# IC555timer.net
KiCad netlist of a schematic drawn in EasyEDA Pro
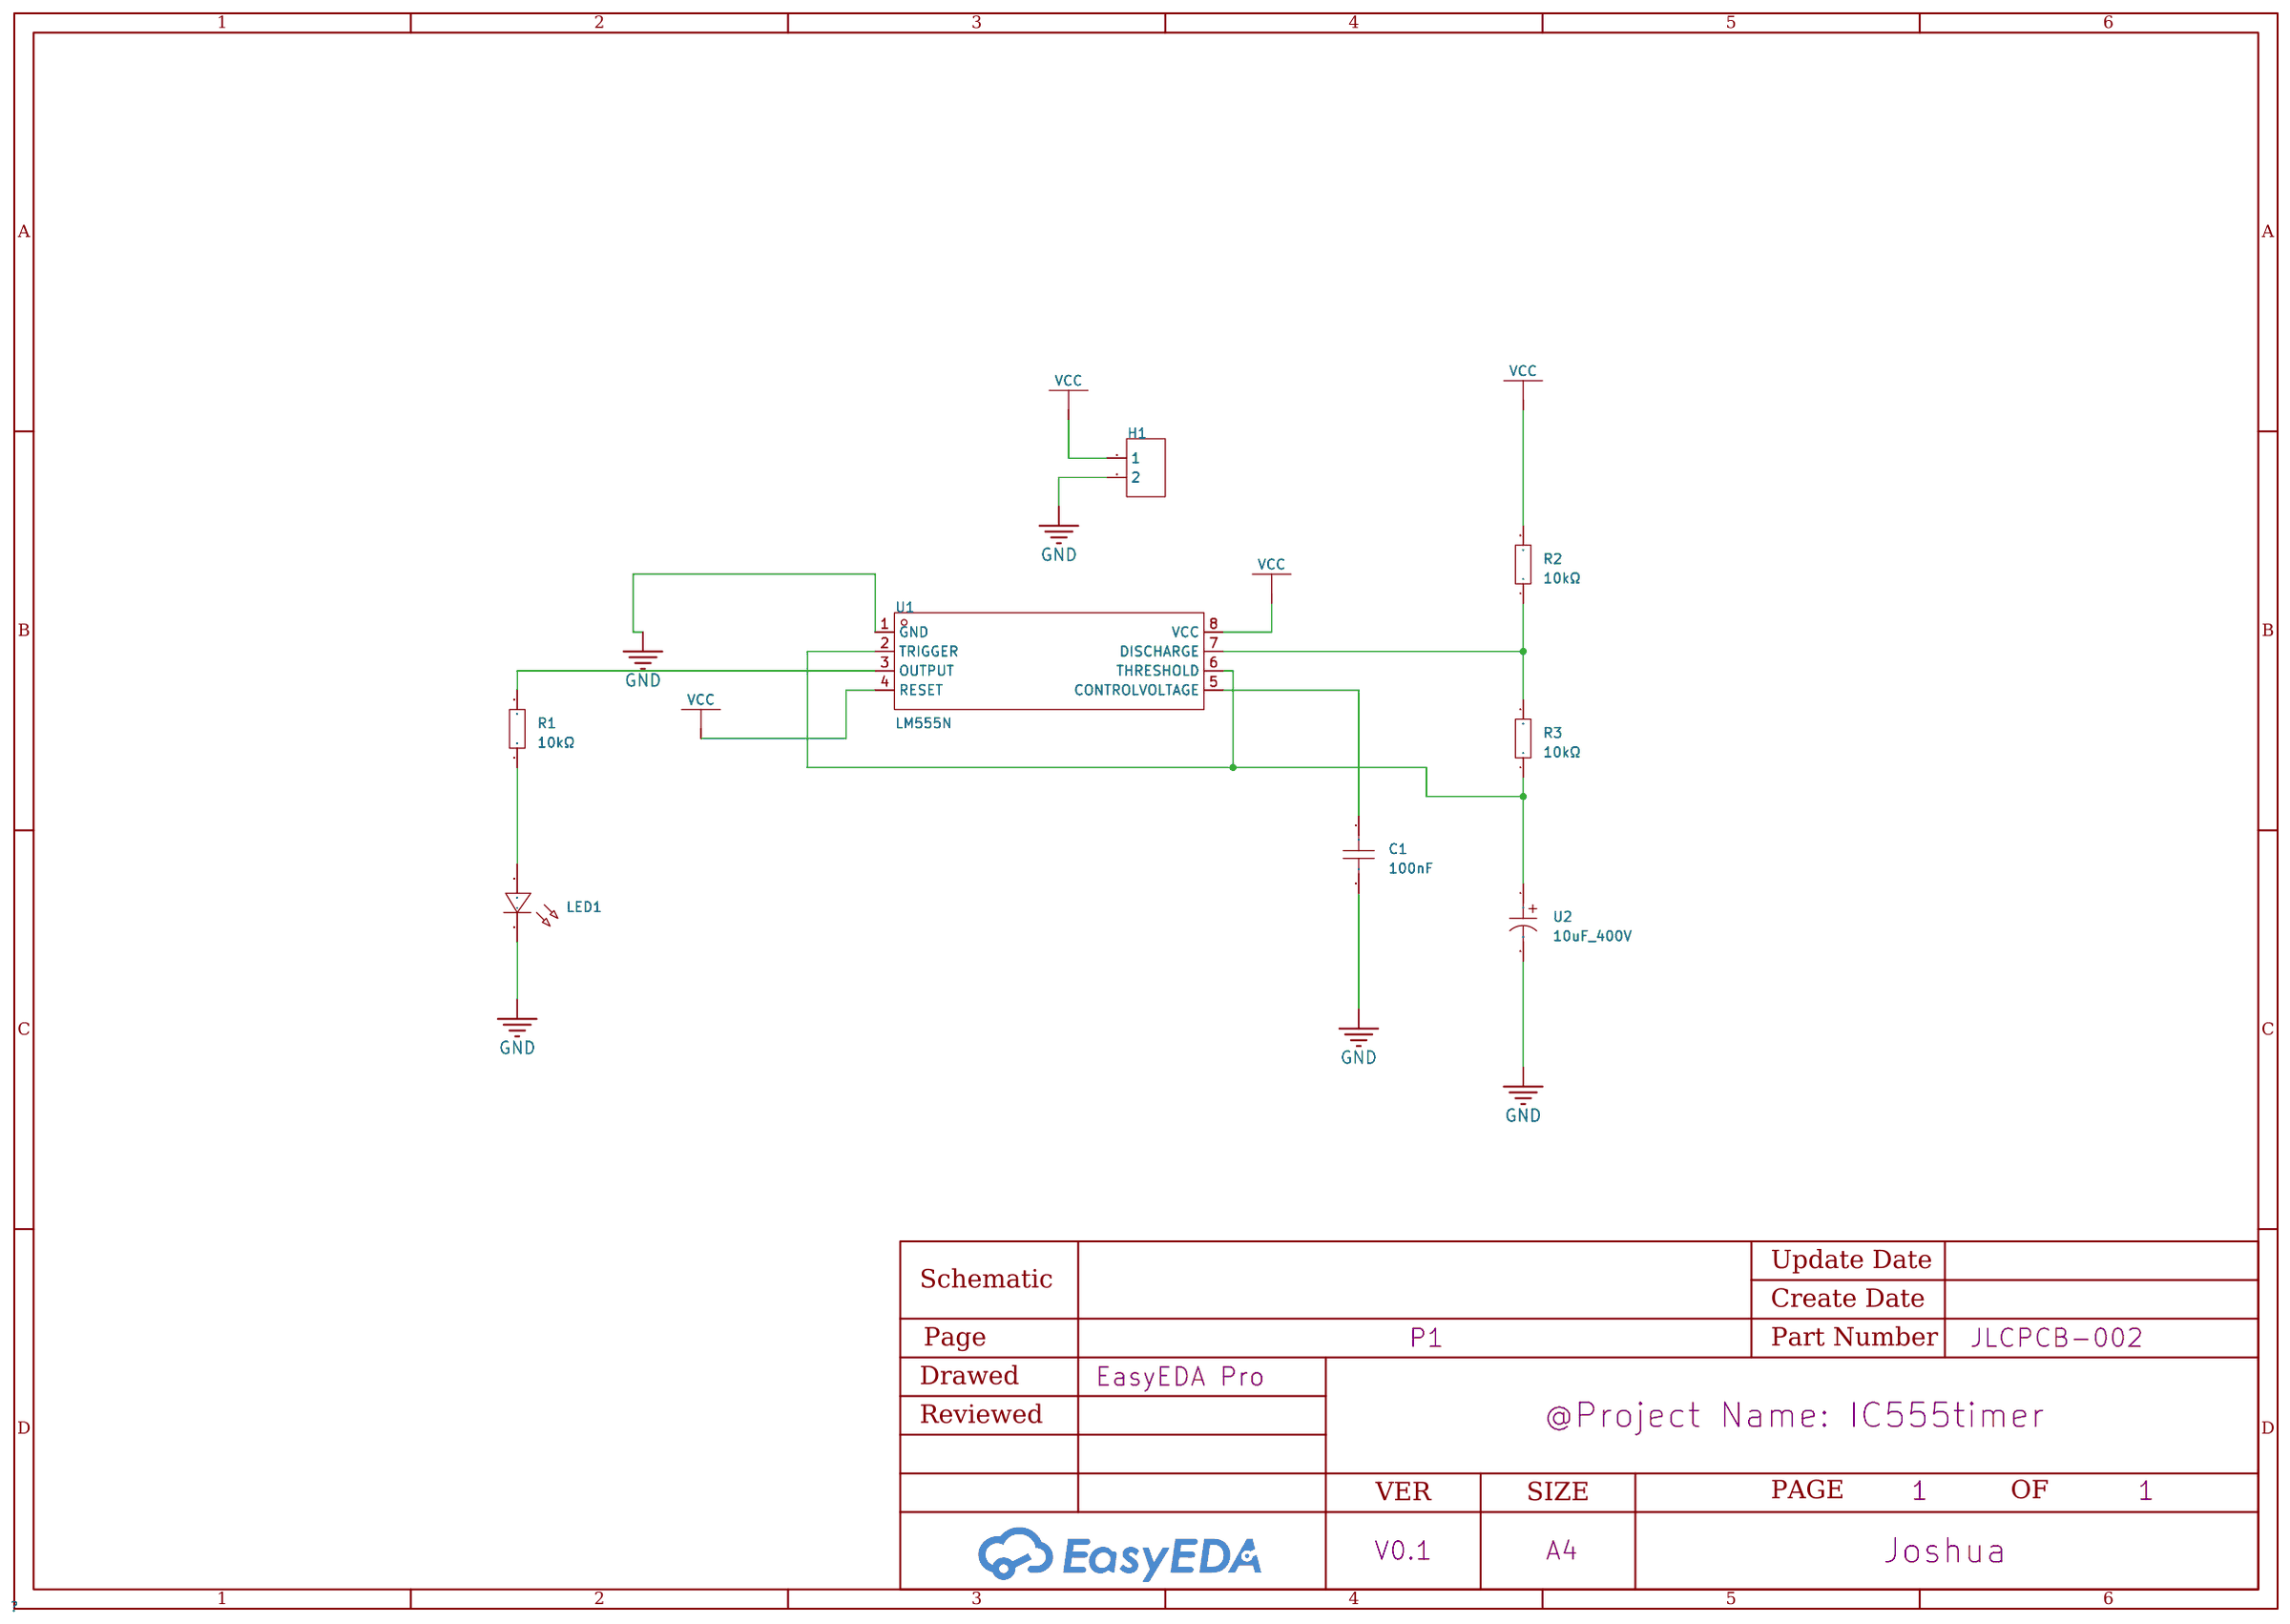
[diagram p0: schematic sheet]

(export (version "E")
  (design (tool "Eeschema 10.0.6"))
  (components
    (comp (ref "C1")
      (value "100nF")
      (footprint "easyedapro:C0201")
      (libsource (lib "easyedapro") (part "CAP"))
    )
    (comp (ref "H1")
      (value "~")
      (footprint "easyedapro:HDR-TH_2P-P2.54-V-F")
      (libsource (lib "easyedapro") (part "Header-Female-2.54_1x2"))
    )
    (comp (ref "LED1")
      (value "~")
      (footprint "easyedapro:LED-TH_BD3.0-P2.54-FD")
      (libsource (lib "easyedapro") (part "LED_TH-R"))
    )
    (comp (ref "R1")
      (value "10kΩ")
      (footprint "easyedapro:RES-TH_BD4.5-L11.5-P15.50-D0.8")
      (libsource (lib "easyedapro") (part "Res"))
    )
    (comp (ref "R2")
      (value "10kΩ")
      (footprint "easyedapro:RES-TH_BD4.5-L11.5-P15.50-D0.8")
      (libsource (lib "easyedapro") (part "Res"))
    )
    (comp (ref "R3")
      (value "10kΩ")
      (footprint "easyedapro:RES-TH_BD4.5-L11.5-P15.50-D0.8")
      (libsource (lib "easyedapro") (part "Res"))
    )
    (comp (ref "U1")
      (value "LM555N")
      (footprint "easyedapro:DIP-8_L9.7-W6.4-P2.54-LS7.6-BL")
      (fields (field (name "Manufacturer") "HGSEMI(华冠)"))
      (libsource (lib "easyedapro") (part "LM555N"))
    )
    (comp (ref "U2")
      (value "10uF_400V")
      (footprint "easyedapro:CAP-TH_BD10.0-P5.00-D0.6-FD")
      (libsource (lib "easyedapro") (part "10UF_400V"))
    )
  )
  (nets
    (net (code "1") (name "GND") (class "Default")
      (node (ref "C1") (pin "2") (pinfunction "2_2") (pintype "input"))
      (node (ref "H1") (pin "2") (pinfunction "2_2") (pintype "input"))
      (node (ref "LED1") (pin "2") (pinfunction "A_2") (pintype "input"))
      (node (ref "U1") (pin "1") (pinfunction "GND_1") (pintype "input"))
      (node (ref "U2") (pin "2") (pinfunction "2_2") (pintype "input"))
    )
    (net (code "2") (name "Net-(LED1-C)") (class "Default")
      (node (ref "LED1") (pin "1") (pinfunction "C_1") (pintype "input"))
      (node (ref "R1") (pin "1") (pinfunction "1_1") (pintype "input"))
    )
    (net (code "3") (name "Net-(U1-CONTROLVOLTAGE)") (class "Default")
      (node (ref "C1") (pin "1") (pinfunction "1_1") (pintype "input"))
      (node (ref "U1") (pin "5") (pinfunction "CONTROLVOLTAGE_5") (pintype "input"))
    )
    (net (code "4") (name "Net-(U1-DISCHARGE)") (class "Default")
      (node (ref "R2") (pin "1") (pinfunction "1_1") (pintype "input"))
      (node (ref "R3") (pin "2") (pinfunction "2_2") (pintype "input"))
      (node (ref "U1") (pin "7") (pinfunction "DISCHARGE_7") (pintype "input"))
    )
    (net (code "5") (name "Net-(U1-OUTPUT)") (class "Default")
      (node (ref "R1") (pin "2") (pinfunction "2_2") (pintype "input"))
      (node (ref "U1") (pin "3") (pinfunction "OUTPUT_3") (pintype "input"))
    )
    (net (code "6") (name "Net-(U1-THRESHOLD)") (class "Default")
      (node (ref "R3") (pin "1") (pinfunction "1_1") (pintype "input"))
      (node (ref "U1") (pin "2") (pinfunction "TRIGGER_2") (pintype "input"))
      (node (ref "U1") (pin "6") (pinfunction "THRESHOLD_6") (pintype "input"))
      (node (ref "U2") (pin "1") (pinfunction "1_1") (pintype "input"))
    )
    (net (code "7") (name "VCC") (class "Default")
      (node (ref "H1") (pin "1") (pinfunction "1_1") (pintype "input"))
      (node (ref "R2") (pin "2") (pinfunction "2_2") (pintype "input"))
      (node (ref "U1") (pin "4") (pinfunction "RESET_4") (pintype "input"))
      (node (ref "U1") (pin "8") (pinfunction "VCC_8") (pintype "input"))
    )
  )
)
